# 00A-110.net
KiCad netlist of a schematic drawn in EAGLE
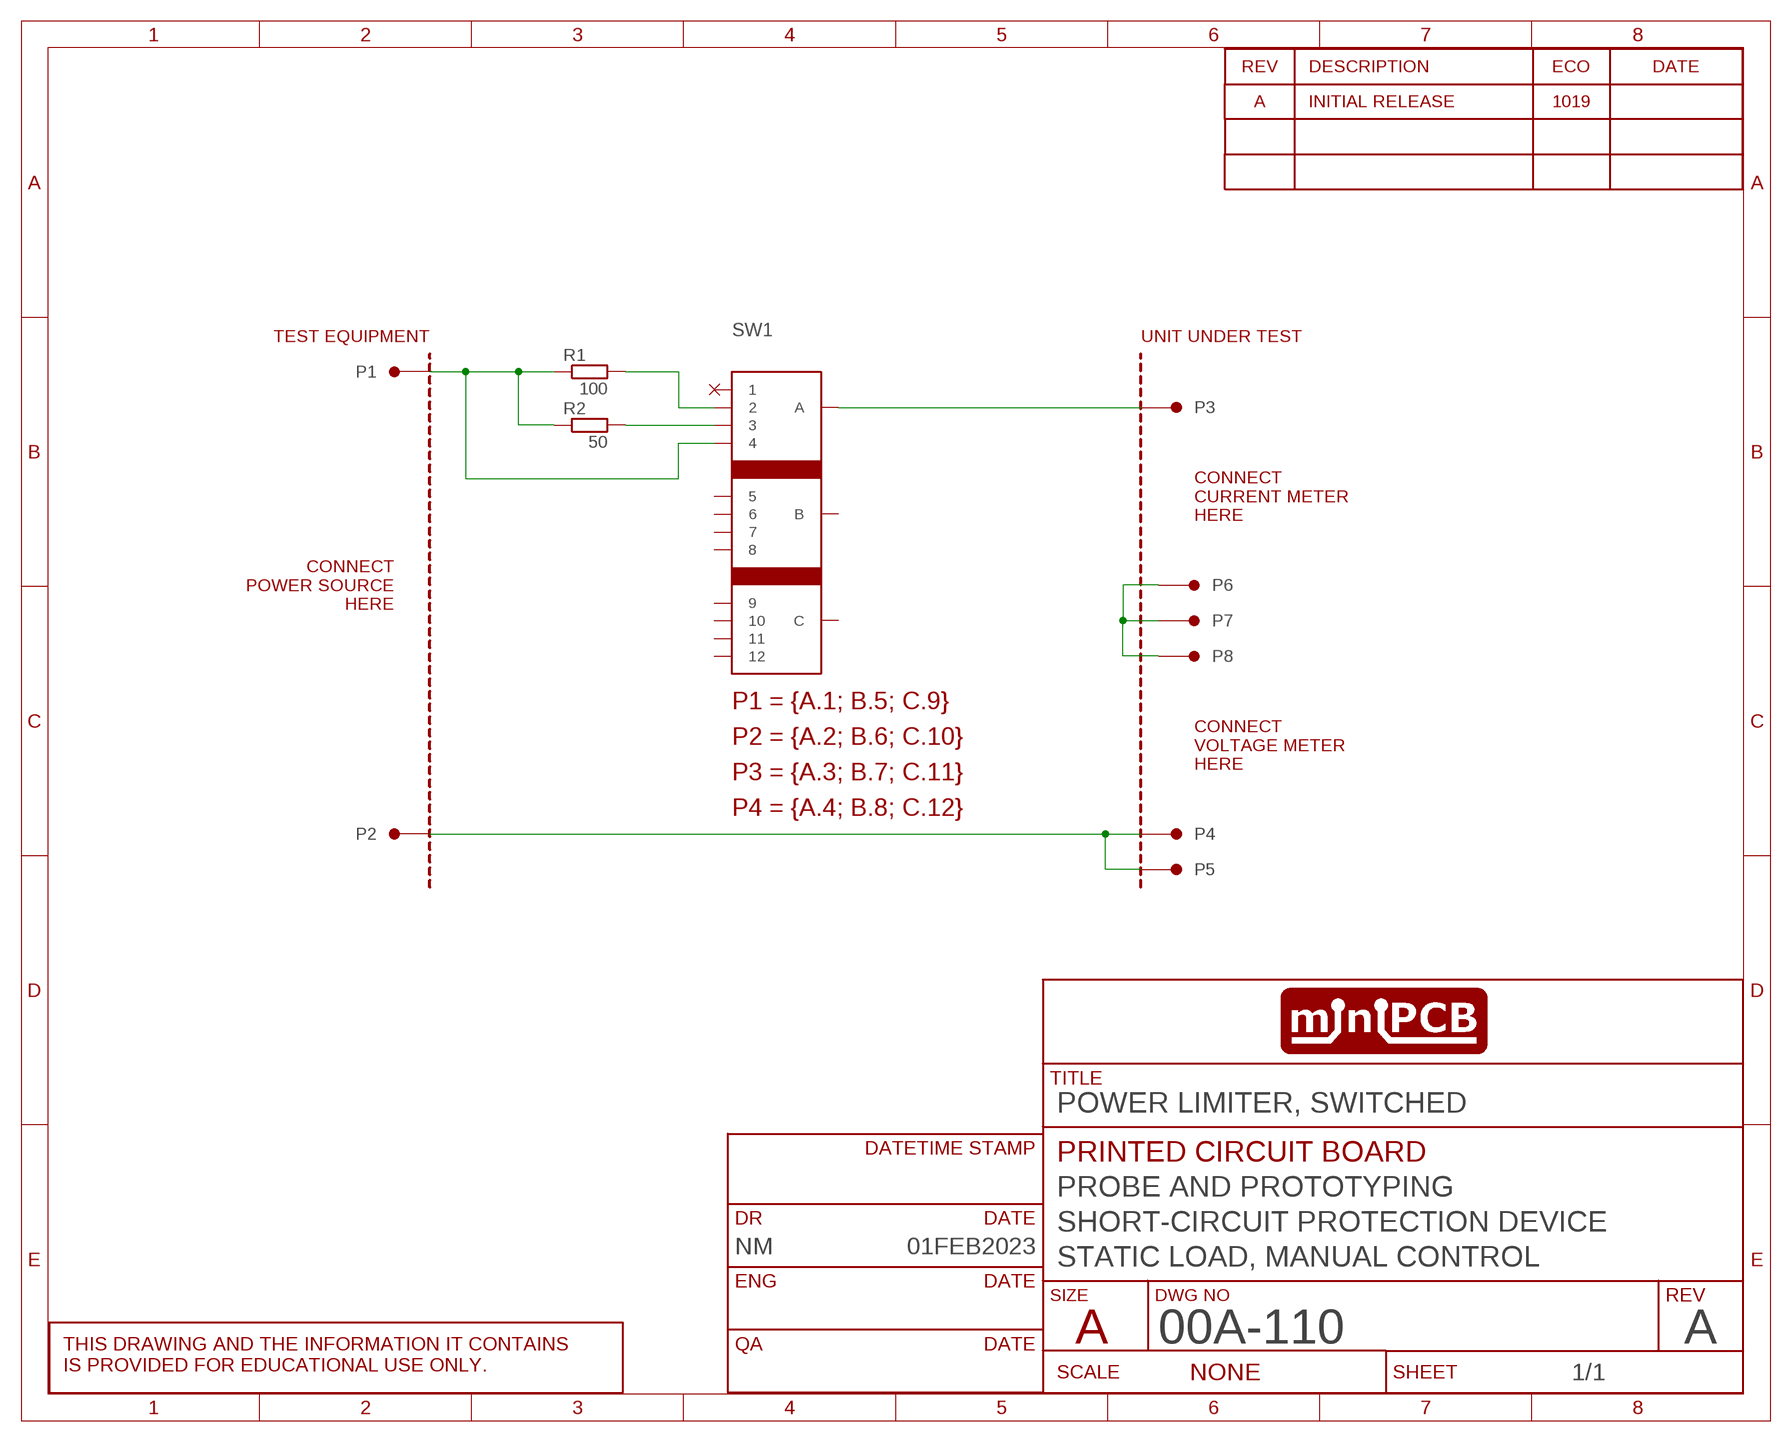
[diagram p0: schematic, sheet 1]

(export (version "E")
  (design (tool "Eeschema 10.0.6"))
  (components
    (comp (ref "P1")
      (value "PINS_15699-0")
      (footprint "eagle-import:BANANAPOST")
      (libsource (lib "eagle-import") (part "PINS_15699-0"))
    )
    (comp (ref "P2")
      (value "PINS_15699-0")
      (footprint "eagle-import:BANANAPOST")
      (libsource (lib "eagle-import") (part "PINS_15699-0"))
    )
    (comp (ref "P3")
      (value "PINS_1KE6060")
      (footprint "eagle-import:PINS_1_KE6060")
      (libsource (lib "eagle-import") (part "PINS_1KE6060"))
    )
    (comp (ref "P4")
      (value "PINS_1KE6060")
      (footprint "eagle-import:PINS_1_KE6060")
      (libsource (lib "eagle-import") (part "PINS_1KE6060"))
    )
    (comp (ref "P5")
      (value "PINS_15699-0")
      (footprint "eagle-import:BANANAPOST")
      (libsource (lib "eagle-import") (part "PINS_15699-0"))
    )
    (comp (ref "P6")
      (value "PINS_1KE6060")
      (footprint "eagle-import:PINS_1_KE6060")
      (libsource (lib "eagle-import") (part "PINS_1KE6060"))
    )
    (comp (ref "P7")
      (value "PINS_1KE6060")
      (footprint "eagle-import:PINS_1_KE6060")
      (libsource (lib "eagle-import") (part "PINS_1KE6060"))
    )
    (comp (ref "P8")
      (value "PINS_15699-0")
      (footprint "eagle-import:BANANAPOST")
      (libsource (lib "eagle-import") (part "PINS_15699-0"))
    )
    (comp (ref "PCB1")
      (value "MINIPCB_0P50X50")
      (footprint "eagle-import:MINIPCB_0P_50X50MM")
      (fields (field (name "PART_NUMBER") "00A-110-A"))
      (libsource (lib "eagle-import") (part "MINIPCB_0P50X50"))
    )
    (comp (ref "R1")
      (value "100")
      (footprint "eagle-import:R-THD-15MM")
      (libsource (lib "eagle-import") (part "RESISTOR15MM"))
    )
    (comp (ref "R2")
      (value "50")
      (footprint "eagle-import:R-THD-15MM")
      (libsource (lib "eagle-import") (part "RESISTOR15MM"))
    )
    (comp (ref "SW1")
      (value "SWITCH-ROTARY-3P4T")
      (footprint "eagle-import:SWITCH-ROTARY-3P4T")
      (libsource (lib "eagle-import") (part "SWITCH-ROTARY-3P4T"))
    )
  )
  (nets
    (net (code "1") (name "Net-(P1-Pad1)") (class "Default")
      (node (ref "P1") (pin "1") (pinfunction "1_1") (pintype "bidirectional"))
      (node (ref "R1") (pin "1") (pinfunction "1_1") (pintype "passive"))
      (node (ref "R2") (pin "1") (pinfunction "1_1") (pintype "passive"))
      (node (ref "SW1") (pin "4") (pinfunction "4_4") (pintype "bidirectional"))
    )
    (net (code "2") (name "Net-(P2-Pad1)") (class "Default")
      (node (ref "P2") (pin "1") (pinfunction "1_1") (pintype "bidirectional"))
      (node (ref "P4") (pin "1") (pinfunction "1_1") (pintype "bidirectional"))
      (node (ref "P4") (pin "2") (pinfunction "1_2") (pintype "bidirectional"))
      (node (ref "P5") (pin "1") (pinfunction "1_1") (pintype "bidirectional"))
    )
    (net (code "3") (name "Net-(P3-1-Pad2)") (class "Default")
      (node (ref "P3") (pin "1") (pinfunction "1_1") (pintype "bidirectional"))
      (node (ref "P3") (pin "2") (pinfunction "1_2") (pintype "bidirectional"))
      (node (ref "SW1") (pin "A") (pinfunction "A_A") (pintype "bidirectional"))
    )
    (net (code "4") (name "Net-(P6-1-Pad2)") (class "Default")
      (node (ref "P6") (pin "1") (pinfunction "1_1") (pintype "bidirectional"))
      (node (ref "P6") (pin "2") (pinfunction "1_2") (pintype "bidirectional"))
      (node (ref "P7") (pin "1") (pinfunction "1_1") (pintype "bidirectional"))
      (node (ref "P7") (pin "2") (pinfunction "1_2") (pintype "bidirectional"))
      (node (ref "P8") (pin "1") (pinfunction "1_1") (pintype "bidirectional"))
    )
    (net (code "5") (name "Net-(R1-Pad2)") (class "Default")
      (node (ref "R1") (pin "2") (pinfunction "2_2") (pintype "passive"))
      (node (ref "SW1") (pin "2") (pinfunction "2_2") (pintype "bidirectional"))
    )
    (net (code "6") (name "Net-(R2-Pad2)") (class "Default")
      (node (ref "R2") (pin "2") (pinfunction "2_2") (pintype "passive"))
      (node (ref "SW1") (pin "3") (pinfunction "3_3") (pintype "bidirectional"))
    )
    (net (code "7") (name "unconnected-(SW1-Pad1)") (class "Default")
      (node (ref "SW1") (pin "1") (pinfunction "1_1") (pintype "bidirectional"))
    )
    (net (code "8") (name "unconnected-(SW1-Pad5)") (class "Default")
      (node (ref "SW1") (pin "5") (pinfunction "5_5") (pintype "bidirectional"))
    )
    (net (code "9") (name "unconnected-(SW1-Pad6)") (class "Default")
      (node (ref "SW1") (pin "6") (pinfunction "6_6") (pintype "bidirectional"))
    )
    (net (code "10") (name "unconnected-(SW1-Pad7)") (class "Default")
      (node (ref "SW1") (pin "7") (pinfunction "7_7") (pintype "bidirectional"))
    )
    (net (code "11") (name "unconnected-(SW1-Pad8)") (class "Default")
      (node (ref "SW1") (pin "8") (pinfunction "8_8") (pintype "bidirectional"))
    )
    (net (code "12") (name "unconnected-(SW1-Pad9)") (class "Default")
      (node (ref "SW1") (pin "9") (pinfunction "9_9") (pintype "bidirectional"))
    )
    (net (code "13") (name "unconnected-(SW1-Pad10)") (class "Default")
      (node (ref "SW1") (pin "10") (pinfunction "10_10") (pintype "bidirectional"))
    )
    (net (code "14") (name "unconnected-(SW1-Pad11)") (class "Default")
      (node (ref "SW1") (pin "11") (pinfunction "11_11") (pintype "bidirectional"))
    )
    (net (code "15") (name "unconnected-(SW1-Pad12)") (class "Default")
      (node (ref "SW1") (pin "12") (pinfunction "12_12") (pintype "bidirectional"))
    )
    (net (code "16") (name "unconnected-(SW1-PadB)") (class "Default")
      (node (ref "SW1") (pin "B") (pinfunction "B_B") (pintype "bidirectional"))
    )
    (net (code "17") (name "unconnected-(SW1-PadC)") (class "Default")
      (node (ref "SW1") (pin "C") (pinfunction "C_C") (pintype "bidirectional"))
    )
  )
)
